# 6d.net
KiCad netlist of a schematic drawn in EAGLE
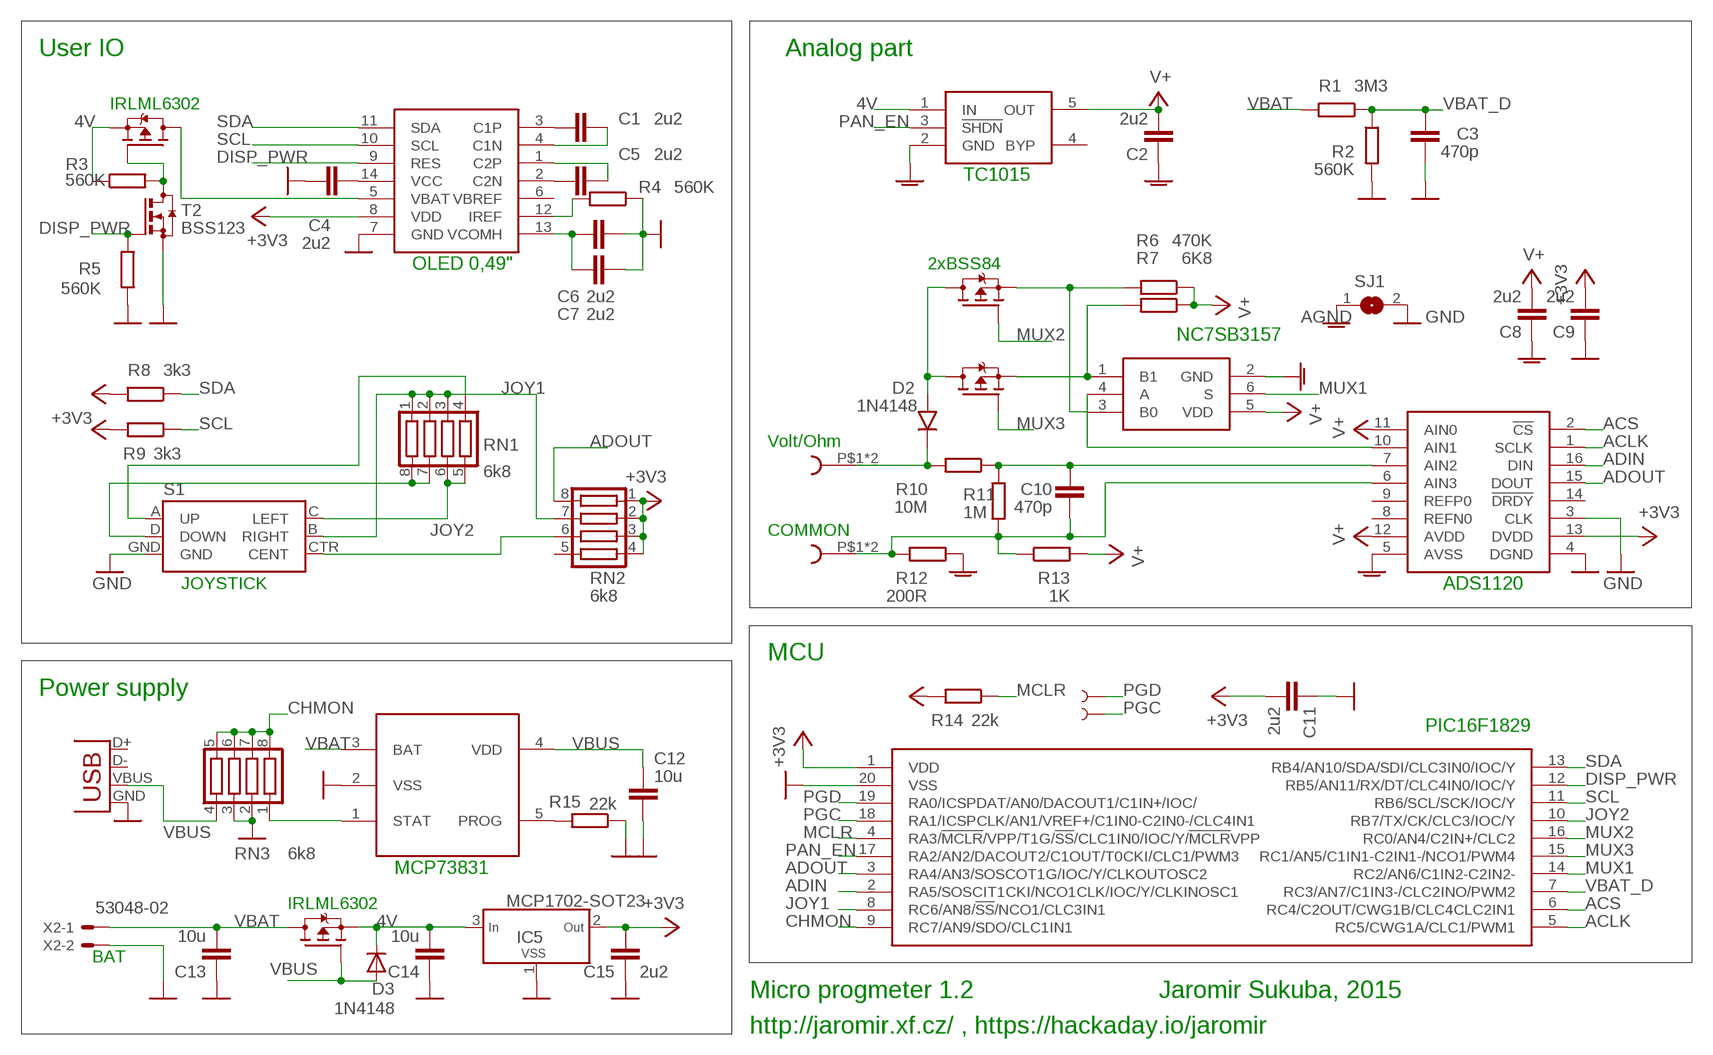
[diagram p0: schematic, sheet 1]

(export (version "E")
  (design (tool "Eeschema 10.0.6"))
  (components
    (comp (ref "C1")
      (value "2u2")
      (footprint "eagle-import:0603")
      (libsource (lib "eagle-import") (part "C_0603"))
    )
    (comp (ref "C2")
      (value "2u2")
      (footprint "eagle-import:0603")
      (libsource (lib "eagle-import") (part "C_0603"))
    )
    (comp (ref "C3")
      (value "470p")
      (footprint "eagle-import:0603")
      (libsource (lib "eagle-import") (part "C_0603"))
    )
    (comp (ref "C4")
      (value "2u2")
      (footprint "eagle-import:0603")
      (libsource (lib "eagle-import") (part "C_0603"))
    )
    (comp (ref "C5")
      (value "2u2")
      (footprint "eagle-import:0603")
      (libsource (lib "eagle-import") (part "C_0603"))
    )
    (comp (ref "C6")
      (value "2u2")
      (footprint "eagle-import:0603")
      (libsource (lib "eagle-import") (part "C_0603"))
    )
    (comp (ref "C7")
      (value "2u2")
      (footprint "eagle-import:0603")
      (libsource (lib "eagle-import") (part "C_0603"))
    )
    (comp (ref "C8")
      (value "2u2")
      (footprint "eagle-import:0603")
      (libsource (lib "eagle-import") (part "C_0603"))
    )
    (comp (ref "C9")
      (value "2u2")
      (footprint "eagle-import:0603")
      (libsource (lib "eagle-import") (part "C_0603"))
    )
    (comp (ref "C10")
      (value "470p")
      (footprint "eagle-import:0603")
      (libsource (lib "eagle-import") (part "C_0603"))
    )
    (comp (ref "C11")
      (value "2u2")
      (footprint "eagle-import:0603")
      (libsource (lib "eagle-import") (part "C_0603"))
    )
    (comp (ref "C12")
      (value "10u")
      (footprint "eagle-import:R0805")
      (libsource (lib "eagle-import") (part "C_0806"))
    )
    (comp (ref "C13")
      (value "10u")
      (footprint "eagle-import:R0805")
      (libsource (lib "eagle-import") (part "C_0806"))
    )
    (comp (ref "C14")
      (value "10u")
      (footprint "eagle-import:R0805")
      (libsource (lib "eagle-import") (part "C_0806"))
    )
    (comp (ref "C15")
      (value "2u2")
      (footprint "eagle-import:0603")
      (libsource (lib "eagle-import") (part "C_0603"))
    )
    (comp (ref "D1")
      (value "DISP_OLED_049B")
      (footprint "eagle-import:DISP_OLED_049_B")
      (libsource (lib "eagle-import") (part "DISP_OLED_049B"))
    )
    (comp (ref "D2")
      (value "1N4148")
      (footprint "eagle-import:SOD-80")
      (libsource (lib "eagle-import") (part "1N4148SOD"))
    )
    (comp (ref "D3")
      (value "1N4148")
      (footprint "eagle-import:SOD123")
      (libsource (lib "eagle-import") (part "DIODE-SOD123"))
    )
    (comp (ref "IC1")
      (value "TC1015")
      (footprint "eagle-import:SOT23-5")
      (libsource (lib "eagle-import") (part "TC1015"))
    )
    (comp (ref "IC2")
      (value "NC7SB3157")
      (footprint "eagle-import:SC70-6")
      (libsource (lib "eagle-import") (part "NC7SB3157"))
    )
    (comp (ref "IC3")
      (value "ADS1120")
      (footprint "eagle-import:TSSOP16")
      (libsource (lib "eagle-import") (part "ADS1120"))
    )
    (comp (ref "IC4")
      (value "PIC16F1508SSOP20")
      (footprint "eagle-import:SSOP20")
      (libsource (lib "eagle-import") (part "PIC16F1508SSOP20"))
    )
    (comp (ref "IC5")
      (value "MCP1702-SOT23")
      (footprint "eagle-import:SOT23")
      (libsource (lib "eagle-import") (part "MCP1702-SOT23"))
    )
    (comp (ref "R1")
      (value "3M3")
      (footprint "eagle-import:0603")
      (libsource (lib "eagle-import") (part "R_0603"))
    )
    (comp (ref "R2")
      (value "560K")
      (footprint "eagle-import:0603")
      (libsource (lib "eagle-import") (part "R_0603"))
    )
    (comp (ref "R3")
      (value "560K")
      (footprint "eagle-import:0603")
      (libsource (lib "eagle-import") (part "R_0603"))
    )
    (comp (ref "R4")
      (value "560K")
      (footprint "eagle-import:0603")
      (libsource (lib "eagle-import") (part "R_0603"))
    )
    (comp (ref "R5")
      (value "560K")
      (footprint "eagle-import:0603")
      (libsource (lib "eagle-import") (part "R_0603"))
    )
    (comp (ref "R6")
      (value "470K")
      (footprint "eagle-import:R0805")
      (libsource (lib "eagle-import") (part "R_0805"))
    )
    (comp (ref "R7")
      (value "6K8")
      (footprint "eagle-import:R0805")
      (libsource (lib "eagle-import") (part "R_0805"))
    )
    (comp (ref "R8")
      (value "3k3")
      (footprint "eagle-import:0603")
      (libsource (lib "eagle-import") (part "R_0603"))
    )
    (comp (ref "R9")
      (value "3k3")
      (footprint "eagle-import:0603")
      (libsource (lib "eagle-import") (part "R_0603"))
    )
    (comp (ref "R10")
      (value "10M")
      (footprint "eagle-import:R0805")
      (libsource (lib "eagle-import") (part "R_0805"))
    )
    (comp (ref "R11")
      (value "1M")
      (footprint "eagle-import:R0805")
      (libsource (lib "eagle-import") (part "R_0805"))
    )
    (comp (ref "R12")
      (value "200R")
      (footprint "eagle-import:0603")
      (libsource (lib "eagle-import") (part "R_0603"))
    )
    (comp (ref "R13")
      (value "1K")
      (footprint "eagle-import:0603")
      (libsource (lib "eagle-import") (part "R_0603"))
    )
    (comp (ref "R14")
      (value "22k")
      (footprint "eagle-import:0603")
      (libsource (lib "eagle-import") (part "R_0603"))
    )
    (comp (ref "R15")
      (value "22k")
      (footprint "eagle-import:0603")
      (libsource (lib "eagle-import") (part "R_0603"))
    )
    (comp (ref "RN1")
      (value "6k8")
      (footprint "eagle-import:CTS742C083")
      (libsource (lib "eagle-import") (part "CTS742C083"))
    )
    (comp (ref "RN2")
      (value "6k8")
      (footprint "eagle-import:CTS742C083")
      (libsource (lib "eagle-import") (part "CTS742C083"))
    )
    (comp (ref "RN3")
      (value "6k8")
      (footprint "eagle-import:CTS742C083")
      (libsource (lib "eagle-import") (part "CTS742C083"))
    )
    (comp (ref "S1")
      (value "JOYSTICK_MINI")
      (footprint "eagle-import:JOYSTICK_MINI")
      (libsource (lib "eagle-import") (part "JOYSTICK_MINI"))
    )
    (comp (ref "SJ1") (value "SJ") (footprint "eagle-import:SJ") (libsource (lib "eagle-import") (part "SJ")))
    (comp (ref "T1")
      (value "BSS84")
      (footprint "eagle-import:SOT23-3")
      (libsource (lib "eagle-import") (part "BSS84"))
    )
    (comp (ref "T2")
      (value "BSS123")
      (footprint "eagle-import:SOT23")
      (libsource (lib "eagle-import") (part "BSS123"))
    )
    (comp (ref "T3")
      (value "BSS84")
      (footprint "eagle-import:SOT23-3")
      (libsource (lib "eagle-import") (part "BSS84"))
    )
    (comp (ref "T4")
      (value "BSS84")
      (footprint "eagle-import:SOT23-3")
      (libsource (lib "eagle-import") (part "BSS84"))
    )
    (comp (ref "T5")
      (value "BSS84")
      (footprint "eagle-import:SOT23-3")
      (libsource (lib "eagle-import") (part "BSS84"))
    )
    (comp (ref "TP1")
      (value "TEST-POINT3X5")
      (footprint "eagle-import:PAD.03X.05")
      (libsource (lib "eagle-import") (part "TEST-POINT3X5"))
    )
    (comp (ref "TP2")
      (value "TEST-POINT3X5")
      (footprint "eagle-import:PAD.03X.05")
      (libsource (lib "eagle-import") (part "TEST-POINT3X5"))
    )
    (comp (ref "U$1")
      (value "BANPLUG_2")
      (footprint "eagle-import:BANPLUG_2")
      (libsource (lib "eagle-import") (part "BANPLUG_2"))
    )
    (comp (ref "U$2")
      (value "BANPLUG_2")
      (footprint "eagle-import:BANPLUG_2")
      (libsource (lib "eagle-import") (part "BANPLUG_2"))
    )
    (comp (ref "U$3")
      (value "MCP73831")
      (footprint "eagle-import:SOT23-5")
      (libsource (lib "eagle-import") (part "MCP73831"))
    )
    (comp (ref "X1")
      (value "USB-MICROB")
      (footprint "eagle-import:USB-MICROB")
      (libsource (lib "eagle-import") (part "USB-MICROB"))
    )
    (comp (ref "X2")
      (value "53048-02")
      (footprint "eagle-import:53048-02")
      (libsource (lib "eagle-import") (part "53?-02048"))
    )
  )
  (nets
    (net (code "1") (name "+3V3") (class "Default")
      (node (ref "C11") (pin "2") (pinfunction "2_2") (pintype "passive"))
      (node (ref "C15") (pin "2") (pinfunction "2_2") (pintype "passive"))
      (node (ref "C9") (pin "2") (pinfunction "2_2") (pintype "passive"))
      (node (ref "D1") (pin "8") (pinfunction "VDD_8") (pintype "bidirectional"))
      (node (ref "IC3") (pin "13") (pinfunction "DVDD_13") (pintype "bidirectional"))
      (node (ref "IC4") (pin "1") (pinfunction "VDD_1") (pintype "bidirectional"))
      (node (ref "IC5") (pin "2") (pinfunction "OUT_2") (pintype "output"))
      (node (ref "R14") (pin "2") (pinfunction "2_2") (pintype "passive"))
      (node (ref "R8") (pin "2") (pinfunction "2_2") (pintype "passive"))
      (node (ref "R9") (pin "2") (pinfunction "2_2") (pintype "passive"))
      (node (ref "RN2") (pin "1") (pinfunction "1_1") (pintype "passive"))
      (node (ref "RN2") (pin "2") (pinfunction "2_2") (pintype "passive"))
      (node (ref "RN2") (pin "3") (pinfunction "3_3") (pintype "passive"))
      (node (ref "RN2") (pin "4") (pinfunction "4_4") (pintype "passive"))
    )
    (net (code "2") (name "/4V") (class "Default")
      (node (ref "C14") (pin "2") (pinfunction "2_2") (pintype "passive"))
      (node (ref "D3") (pin "C") (pinfunction "C_C") (pintype "passive"))
      (node (ref "IC1") (pin "1") (pinfunction "IN_1") (pintype "bidirectional"))
      (node (ref "IC5") (pin "3") (pinfunction "IN_3") (pintype "input"))
      (node (ref "R3") (pin "1") (pinfunction "1_1") (pintype "passive"))
      (node (ref "T1") (pin "2") (pinfunction "S_2") (pintype "passive"))
      (node (ref "T5") (pin "2") (pinfunction "S_2") (pintype "passive"))
    )
    (net (code "3") (name "/ACLK") (class "Default")
      (node (ref "IC3") (pin "1") (pinfunction "SCLK_1") (pintype "bidirectional"))
      (node (ref "IC4") (pin "5") (pinfunction "RC5/CWG1A/CLC1/PWM1_5") (pintype "bidirectional"))
    )
    (net (code "4") (name "/ACS") (class "Default")
      (node (ref "IC3") (pin "2") (pinfunction "~{CS}_2") (pintype "bidirectional"))
      (node (ref "IC4") (pin "6") (pinfunction "RC4/C2OUT/CWG1B/CLC4CLC2IN1_6") (pintype "bidirectional"))
    )
    (net (code "5") (name "/ADIN") (class "Default")
      (node (ref "IC3") (pin "16") (pinfunction "DIN_16") (pintype "bidirectional"))
      (node (ref "IC4") (pin "2") (pinfunction "RA5/SOSCIT1CKI/NCO1CLK/IOC/Y/CLKINOSC1_2") (pintype "bidirectional"))
    )
    (net (code "6") (name "/ADOUT") (class "Default")
      (node (ref "IC3") (pin "15") (pinfunction "DOUT_15") (pintype "bidirectional"))
      (node (ref "IC4") (pin "3") (pinfunction "RA4/AN3/SOSCOT1G/IOC/Y/CLKOUTOSC2_3") (pintype "bidirectional"))
      (node (ref "RN2") (pin "8") (pinfunction "8_8") (pintype "passive"))
    )
    (net (code "7") (name "/CHMON") (class "Default")
      (node (ref "IC4") (pin "9") (pinfunction "RC7/AN9/SDO/CLC1IN1_9") (pintype "bidirectional"))
      (node (ref "RN3") (pin "5") (pinfunction "5_5") (pintype "passive"))
      (node (ref "RN3") (pin "6") (pinfunction "6_6") (pintype "passive"))
      (node (ref "RN3") (pin "7") (pinfunction "7_7") (pintype "passive"))
      (node (ref "RN3") (pin "8") (pinfunction "8_8") (pintype "passive"))
    )
    (net (code "8") (name "/DISP_PWR") (class "Default")
      (node (ref "D1") (pin "9") (pinfunction "RES_9") (pintype "bidirectional"))
      (node (ref "IC4") (pin "12") (pinfunction "RB5/AN11/RX/DT/CLC4IN0/IOC/Y_12") (pintype "bidirectional"))
      (node (ref "R5") (pin "2") (pinfunction "2_2") (pintype "passive"))
      (node (ref "T2") (pin "1") (pinfunction "G_1") (pintype "passive"))
    )
    (net (code "9") (name "/JOY1") (class "Default")
      (node (ref "IC4") (pin "8") (pinfunction "RC6/AN8/~{SS}/NCO1/CLC3IN1_8") (pintype "bidirectional"))
      (node (ref "RN1") (pin "1") (pinfunction "1_1") (pintype "passive"))
      (node (ref "RN1") (pin "2") (pinfunction "2_2") (pintype "passive"))
      (node (ref "RN1") (pin "3") (pinfunction "3_3") (pintype "passive"))
      (node (ref "RN2") (pin "7") (pinfunction "7_7") (pintype "passive"))
      (node (ref "S1") (pin "B") (pinfunction "RIGHT_B") (pintype "bidirectional"))
    )
    (net (code "10") (name "/JOY2") (class "Default")
      (node (ref "IC4") (pin "10") (pinfunction "RB7/TX/CK/CLC3/IOC/Y_10") (pintype "bidirectional"))
      (node (ref "RN2") (pin "6") (pinfunction "6_6") (pintype "passive"))
      (node (ref "S1") (pin "CTR") (pinfunction "CENT_CTR") (pintype "bidirectional"))
    )
    (net (code "11") (name "/MCLR") (class "Default")
      (node (ref "IC4") (pin "4") (pinfunction "RA3/~{MCLR}/VPP/T1G/~{SS}/CLC1IN0/IOC/Y/~{MCLR}VPP_4") (pintype "bidirectional"))
      (node (ref "R14") (pin "1") (pinfunction "1_1") (pintype "passive"))
    )
    (net (code "12") (name "/MUX1") (class "Default")
      (node (ref "IC2") (pin "6") (pinfunction "S_6") (pintype "bidirectional"))
      (node (ref "IC4") (pin "14") (pinfunction "RC2/AN6/C1IN2-C2IN2-_14") (pintype "bidirectional"))
    )
    (net (code "13") (name "/MUX2") (class "Default")
      (node (ref "IC4") (pin "16") (pinfunction "RC0/AN4/C2IN+/CLC2_16") (pintype "bidirectional"))
      (node (ref "T3") (pin "1") (pinfunction "G_1") (pintype "passive"))
    )
    (net (code "14") (name "/MUX3") (class "Default")
      (node (ref "IC4") (pin "15") (pinfunction "RC1/AN5/C1IN1-C2IN1-/NCO1/PWM4_15") (pintype "bidirectional"))
      (node (ref "T4") (pin "1") (pinfunction "G_1") (pintype "passive"))
    )
    (net (code "15") (name "/PAN_EN") (class "Default")
      (node (ref "IC1") (pin "3") (pinfunction "~{SHDN}_3") (pintype "bidirectional"))
      (node (ref "IC4") (pin "17") (pinfunction "RA2/AN2/DACOUT2/C1OUT/T0CKI/CLC1/PWM3_17") (pintype "bidirectional"))
    )
    (net (code "16") (name "/PGC") (class "Default")
      (node (ref "IC4") (pin "18") (pinfunction "RA1/ICSPCLK/AN1/VREF+/C1IN0-C2IN0-/CLC4IN1_18") (pintype "bidirectional"))
      (node (ref "TP2") (pin "P$1") (pinfunction "1_P$1") (pintype "bidirectional"))
    )
    (net (code "17") (name "/PGD") (class "Default")
      (node (ref "IC4") (pin "19") (pinfunction "RA0/ICSPDAT/AN0/DACOUT1/C1IN+/IOC/_19") (pintype "bidirectional"))
      (node (ref "TP1") (pin "P$1") (pinfunction "1_P$1") (pintype "bidirectional"))
    )
    (net (code "18") (name "/SCL") (class "Default")
      (node (ref "D1") (pin "10") (pinfunction "SCL_10") (pintype "bidirectional"))
      (node (ref "IC4") (pin "11") (pinfunction "RB6/SCL/SCK/IOC/Y_11") (pintype "bidirectional"))
      (node (ref "R9") (pin "1") (pinfunction "1_1") (pintype "passive"))
    )
    (net (code "19") (name "/SDA") (class "Default")
      (node (ref "D1") (pin "11") (pinfunction "SDA_11") (pintype "bidirectional"))
      (node (ref "IC4") (pin "13") (pinfunction "RB4/AN10/SDA/SDI/CLC3IN0/IOC/Y_13") (pintype "bidirectional"))
      (node (ref "R8") (pin "1") (pinfunction "1_1") (pintype "passive"))
    )
    (net (code "20") (name "/VBAT") (class "Default")
      (node (ref "C13") (pin "2") (pinfunction "2_2") (pintype "passive"))
      (node (ref "R1") (pin "2") (pinfunction "2_2") (pintype "passive"))
      (node (ref "T5") (pin "3") (pinfunction "D_3") (pintype "passive"))
      (node (ref "U$3") (pin "3") (pinfunction "BAT_3") (pintype "bidirectional"))
      (node (ref "X2") (pin "1") (pinfunction "S_1") (pintype "passive"))
    )
    (net (code "21") (name "/VBAT_D") (class "Default")
      (node (ref "C3") (pin "2") (pinfunction "2_2") (pintype "passive"))
      (node (ref "IC4") (pin "7") (pinfunction "RC3/AN7/C1IN3-/CLC2INO/PWM2_7") (pintype "bidirectional"))
      (node (ref "R1") (pin "1") (pinfunction "1_1") (pintype "passive"))
      (node (ref "R2") (pin "1") (pinfunction "1_1") (pintype "passive"))
    )
    (net (code "22") (name "/VBUS") (class "Default")
      (node (ref "C12") (pin "1") (pinfunction "1_1") (pintype "passive"))
      (node (ref "D3") (pin "A") (pinfunction "A_A") (pintype "passive"))
      (node (ref "RN3") (pin "4") (pinfunction "4_4") (pintype "passive"))
      (node (ref "T5") (pin "1") (pinfunction "G_1") (pintype "passive"))
      (node (ref "U$3") (pin "4") (pinfunction "VDD_4") (pintype "bidirectional"))
      (node (ref "X1") (pin "VBUS") (pinfunction "VBUS_VBUS") (pintype "bidirectional"))
    )
    (net (code "23") (name "AGND") (class "Default")
      (node (ref "C2") (pin "1") (pinfunction "1_1") (pintype "passive"))
      (node (ref "C8") (pin "1") (pinfunction "1_1") (pintype "passive"))
      (node (ref "IC1") (pin "2") (pinfunction "GND_2") (pintype "bidirectional"))
      (node (ref "IC2") (pin "2") (pinfunction "GND_2") (pintype "bidirectional"))
      (node (ref "IC3") (pin "5") (pinfunction "AVSS_5") (pintype "bidirectional"))
      (node (ref "R12") (pin "1") (pinfunction "1_1") (pintype "passive"))
      (node (ref "SJ1") (pin "1") (pinfunction "1_1") (pintype "passive"))
    )
    (net (code "24") (name "GND") (class "Default")
      (node (ref "C11") (pin "1") (pinfunction "1_1") (pintype "passive"))
      (node (ref "C12") (pin "2") (pinfunction "2_2") (pintype "passive"))
      (node (ref "C13") (pin "1") (pinfunction "1_1") (pintype "passive"))
      (node (ref "C14") (pin "1") (pinfunction "1_1") (pintype "passive"))
      (node (ref "C15") (pin "1") (pinfunction "1_1") (pintype "passive"))
      (node (ref "C3") (pin "1") (pinfunction "1_1") (pintype "passive"))
      (node (ref "C4") (pin "1") (pinfunction "1_1") (pintype "passive"))
      (node (ref "C6") (pin "2") (pinfunction "2_2") (pintype "passive"))
      (node (ref "C7") (pin "2") (pinfunction "2_2") (pintype "passive"))
      (node (ref "C9") (pin "1") (pinfunction "1_1") (pintype "passive"))
      (node (ref "D1") (pin "7") (pinfunction "GND_7") (pintype "bidirectional"))
      (node (ref "IC3") (pin "3") (pinfunction "CLK_3") (pintype "bidirectional"))
      (node (ref "IC3") (pin "4") (pinfunction "DGND_4") (pintype "bidirectional"))
      (node (ref "IC4") (pin "20") (pinfunction "VSS_20") (pintype "bidirectional"))
      (node (ref "IC5") (pin "1") (pinfunction "VSS_1") (pintype "input"))
      (node (ref "R15") (pin "1") (pinfunction "1_1") (pintype "passive"))
      (node (ref "R2") (pin "2") (pinfunction "2_2") (pintype "passive"))
      (node (ref "R4") (pin "1") (pinfunction "1_1") (pintype "passive"))
      (node (ref "R5") (pin "1") (pinfunction "1_1") (pintype "passive"))
      (node (ref "RN3") (pin "2") (pinfunction "2_2") (pintype "passive"))
      (node (ref "RN3") (pin "3") (pinfunction "3_3") (pintype "passive"))
      (node (ref "S1") (pin "GND") (pinfunction "GND_GND") (pintype "bidirectional"))
      (node (ref "SJ1") (pin "2") (pinfunction "2_2") (pintype "passive"))
      (node (ref "T2") (pin "2") (pinfunction "S_2") (pintype "passive"))
      (node (ref "U$3") (pin "2") (pinfunction "VSS_2") (pintype "bidirectional"))
      (node (ref "X1") (pin "GND") (pinfunction "GND_GND") (pintype "bidirectional"))
      (node (ref "X2") (pin "2") (pinfunction "S_2") (pintype "passive"))
    )
    (net (code "25") (name "Net-(D1-C1N)") (class "Default")
      (node (ref "C1") (pin "2") (pinfunction "2_2") (pintype "passive"))
      (node (ref "D1") (pin "4") (pinfunction "C1N_4") (pintype "bidirectional"))
    )
    (net (code "26") (name "Net-(D1-C1P)") (class "Default")
      (node (ref "C1") (pin "1") (pinfunction "1_1") (pintype "passive"))
      (node (ref "D1") (pin "3") (pinfunction "C1P_3") (pintype "bidirectional"))
    )
    (net (code "27") (name "Net-(D1-C2N)") (class "Default")
      (node (ref "C5") (pin "1") (pinfunction "1_1") (pintype "passive"))
      (node (ref "D1") (pin "2") (pinfunction "C2N_2") (pintype "bidirectional"))
    )
    (net (code "28") (name "Net-(D1-C2P)") (class "Default")
      (node (ref "C5") (pin "2") (pinfunction "2_2") (pintype "passive"))
      (node (ref "D1") (pin "1") (pinfunction "C2P_1") (pintype "bidirectional"))
    )
    (net (code "29") (name "Net-(D1-IREF)") (class "Default")
      (node (ref "D1") (pin "12") (pinfunction "IREF_12") (pintype "bidirectional"))
      (node (ref "R4") (pin "2") (pinfunction "2_2") (pintype "passive"))
    )
    (net (code "30") (name "Net-(D1-VBAT)") (class "Default")
      (node (ref "D1") (pin "5") (pinfunction "VBAT_5") (pintype "bidirectional"))
      (node (ref "T1") (pin "3") (pinfunction "D_3") (pintype "passive"))
    )
    (net (code "31") (name "Net-(D1-VCC)") (class "Default")
      (node (ref "C4") (pin "2") (pinfunction "2_2") (pintype "passive"))
      (node (ref "D1") (pin "14") (pinfunction "VCC_14") (pintype "bidirectional"))
    )
    (net (code "32") (name "Net-(D1-VCOMH)") (class "Default")
      (node (ref "C6") (pin "1") (pinfunction "1_1") (pintype "passive"))
      (node (ref "C7") (pin "1") (pinfunction "1_1") (pintype "passive"))
      (node (ref "D1") (pin "13") (pinfunction "VCOMH_13") (pintype "bidirectional"))
    )
    (net (code "33") (name "Net-(D2-PadK)") (class "Default")
      (node (ref "D2") (pin "K") (pinfunction "K_K") (pintype "output"))
      (node (ref "R10") (pin "2") (pinfunction "2_2") (pintype "passive"))
      (node (ref "U$1") (pin "P$1") (pinfunction "P$1_P$1") (pintype "bidirectional"))
      (node (ref "U$1") (pin "P$2") (pinfunction "P$1_P$2") (pintype "bidirectional"))
    )
    (net (code "34") (name "Net-(IC2-A)") (class "Default")
      (node (ref "IC2") (pin "4") (pinfunction "A_4") (pintype "bidirectional"))
      (node (ref "IC3") (pin "10") (pinfunction "AIN1_10") (pintype "bidirectional"))
    )
    (net (code "35") (name "Net-(IC2-B0)") (class "Default")
      (node (ref "IC2") (pin "3") (pinfunction "B0_3") (pintype "bidirectional"))
      (node (ref "R6") (pin "2") (pinfunction "2_2") (pintype "passive"))
      (node (ref "T3") (pin "2") (pinfunction "S_2") (pintype "passive"))
    )
    (net (code "36") (name "Net-(IC2-B1)") (class "Default")
      (node (ref "IC2") (pin "1") (pinfunction "B1_1") (pintype "bidirectional"))
      (node (ref "R7") (pin "2") (pinfunction "2_2") (pintype "passive"))
      (node (ref "T4") (pin "2") (pinfunction "S_2") (pintype "passive"))
    )
    (net (code "37") (name "Net-(IC3-AIN2)") (class "Default")
      (node (ref "C10") (pin "2") (pinfunction "2_2") (pintype "passive"))
      (node (ref "IC3") (pin "7") (pinfunction "AIN2_7") (pintype "bidirectional"))
      (node (ref "R10") (pin "1") (pinfunction "1_1") (pintype "passive"))
      (node (ref "R11") (pin "1") (pinfunction "1_1") (pintype "passive"))
    )
    (net (code "38") (name "Net-(IC3-AIN3)") (class "Default")
      (node (ref "C10") (pin "1") (pinfunction "1_1") (pintype "passive"))
      (node (ref "IC3") (pin "6") (pinfunction "AIN3_6") (pintype "bidirectional"))
      (node (ref "R11") (pin "2") (pinfunction "2_2") (pintype "passive"))
      (node (ref "R12") (pin "2") (pinfunction "2_2") (pintype "passive"))
      (node (ref "R13") (pin "1") (pinfunction "1_1") (pintype "passive"))
      (node (ref "U$2") (pin "P$1") (pinfunction "P$1_P$1") (pintype "bidirectional"))
      (node (ref "U$2") (pin "P$2") (pinfunction "P$1_P$2") (pintype "bidirectional"))
    )
    (net (code "39") (name "Net-(S1-DOWN)") (class "Default")
      (node (ref "RN1") (pin "7") (pinfunction "7_7") (pintype "passive"))
      (node (ref "RN1") (pin "8") (pinfunction "8_8") (pintype "passive"))
      (node (ref "S1") (pin "D") (pinfunction "DOWN_D") (pintype "bidirectional"))
    )
    (net (code "40") (name "Net-(S1-LEFT)") (class "Default")
      (node (ref "RN1") (pin "5") (pinfunction "5_5") (pintype "passive"))
      (node (ref "RN1") (pin "6") (pinfunction "6_6") (pintype "passive"))
      (node (ref "S1") (pin "C") (pinfunction "LEFT_C") (pintype "bidirectional"))
    )
    (net (code "41") (name "Net-(S1-UP)") (class "Default")
      (node (ref "RN1") (pin "4") (pinfunction "4_4") (pintype "passive"))
      (node (ref "S1") (pin "A") (pinfunction "UP_A") (pintype "bidirectional"))
    )
    (net (code "42") (name "Net-(T1-G)") (class "Default")
      (node (ref "R3") (pin "2") (pinfunction "2_2") (pintype "passive"))
      (node (ref "T1") (pin "1") (pinfunction "G_1") (pintype "passive"))
      (node (ref "T2") (pin "3") (pinfunction "D_3") (pintype "passive"))
    )
    (net (code "43") (name "Net-(T3-D)") (class "Default")
      (node (ref "D2") (pin "A") (pinfunction "A_A") (pintype "input"))
      (node (ref "T3") (pin "3") (pinfunction "D_3") (pintype "passive"))
      (node (ref "T4") (pin "3") (pinfunction "D_3") (pintype "passive"))
    )
    (net (code "44") (name "Net-(U$3-PROG)") (class "Default")
      (node (ref "R15") (pin "2") (pinfunction "2_2") (pintype "passive"))
      (node (ref "U$3") (pin "5") (pinfunction "PROG_5") (pintype "bidirectional"))
    )
    (net (code "45") (name "Net-(U$3-STAT)") (class "Default")
      (node (ref "RN3") (pin "1") (pinfunction "1_1") (pintype "passive"))
      (node (ref "U$3") (pin "1") (pinfunction "STAT_1") (pintype "bidirectional"))
    )
    (net (code "46") (name "V+") (class "Default")
      (node (ref "C2") (pin "2") (pinfunction "2_2") (pintype "passive"))
      (node (ref "C8") (pin "2") (pinfunction "2_2") (pintype "passive"))
      (node (ref "IC1") (pin "5") (pinfunction "OUT_5") (pintype "bidirectional"))
      (node (ref "IC2") (pin "5") (pinfunction "VDD_5") (pintype "bidirectional"))
      (node (ref "IC3") (pin "11") (pinfunction "AIN0_11") (pintype "bidirectional"))
      (node (ref "IC3") (pin "12") (pinfunction "AVDD_12") (pintype "bidirectional"))
      (node (ref "R13") (pin "2") (pinfunction "2_2") (pintype "passive"))
      (node (ref "R6") (pin "1") (pinfunction "1_1") (pintype "passive"))
      (node (ref "R7") (pin "1") (pinfunction "1_1") (pintype "passive"))
    )
    (net (code "47") (name "unconnected-(D1-VBREF-Pad6)") (class "Default")
      (node (ref "D1") (pin "6") (pinfunction "VBREF_6") (pintype "bidirectional"))
    )
    (net (code "48") (name "unconnected-(IC1-BYP-Pad4)") (class "Default")
      (node (ref "IC1") (pin "4") (pinfunction "BYP_4") (pintype "bidirectional"))
    )
    (net (code "49") (name "unconnected-(IC3-REFN0-Pad8)") (class "Default")
      (node (ref "IC3") (pin "8") (pinfunction "REFN0_8") (pintype "bidirectional"))
    )
    (net (code "50") (name "unconnected-(IC3-REFP0-Pad9)") (class "Default")
      (node (ref "IC3") (pin "9") (pinfunction "REFP0_9") (pintype "bidirectional"))
    )
    (net (code "51") (name "unconnected-(IC3-~{DRDY}-Pad14)") (class "Default")
      (node (ref "IC3") (pin "14") (pinfunction "~{DRDY}_14") (pintype "bidirectional"))
    )
    (net (code "52") (name "unconnected-(RN2-Pad5)") (class "Default")
      (node (ref "RN2") (pin "5") (pinfunction "5_5") (pintype "passive"))
    )
    (net (code "53") (name "unconnected-(X1-PadD+)") (class "Default")
      (node (ref "X1") (pin "D+") (pinfunction "D+_D+") (pintype "bidirectional"))
    )
    (net (code "54") (name "unconnected-(X1-PadD-)") (class "Default")
      (node (ref "X1") (pin "D-") (pinfunction "D-_D-") (pintype "bidirectional"))
    )
  )
)
